# Schematic.net
KiCad netlist of a schematic drawn in Altium Designer
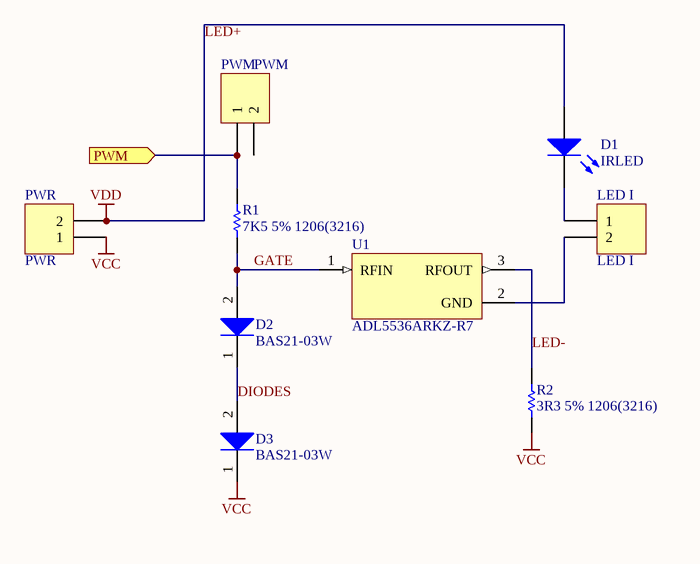
[diagram p0: Schematic.SchDoc]

(export (version "E")
  (design (tool "Eeschema 10.0.6"))
  (components
    (comp (ref "D1")
      (value "IRLED")
      (footprint "LED-1")
      (description "Typical RED GaAs LED")
      (fields (field (name "PUBLISHER") "Altium Limited"))
      (libsource (lib "Miscellaneous Devices") (part "LED1"))
    )
    (comp (ref "D2")
      (value "BAS21-03W")
      (footprint "INF-SOD323_V")
      (description "Silicon Switching Diode, SOD323, Reel, Green")
      (fields (field (name "MANUFACTURER") "Infineon"))
      (libsource (lib "Altium Inc") (part "CMP-1176-00009-1"))
    )
    (comp (ref "D3")
      (value "BAS21-03W")
      (footprint "INF-SOD323_V")
      (description "Silicon Switching Diode, SOD323, Reel, Green")
      (fields (field (name "MANUFACTURER") "Infineon"))
      (libsource (lib "Altium Inc") (part "CMP-1176-00009-1"))
    )
    (comp (ref "LED I")
      (value "LED I")
      (footprint "HDR1X2")
      (description "Header, 2-Pin")
      (fields (field (name "PUBLISHER") "Altium Limited"))
      (libsource (lib "Miscellaneous Connectors") (part "Header 2"))
    )
    (comp (ref "PWM")
      (value "PWM")
      (footprint "HDR1X2")
      (description "Header, 2-Pin")
      (fields (field (name "PUBLISHER") "Altium Limited"))
      (libsource (lib "") (part "Header 2_2"))
    )
    (comp (ref "PWR")
      (value "PWR")
      (footprint "HDR1X2")
      (description "Header, 2-Pin")
      (fields (field (name "PUBLISHER") "Altium Limited"))
      (libsource (lib "") (part "Header 2_1"))
    )
    (comp (ref "R1")
      (value "7K5 5% 1206(3216)")
      (footprint "RESC1206(3216)_N")
      (description "7K5 0.25W 5% 1206 (3216 Metric)  SMD")
      (fields (field (name "POWER") "0.25 W") (field (name "TOLERANCE") "5 %"))
      (libsource (lib "Altium Inc") (part "RES"))
    )
    (comp (ref "R2")
      (value "3R3 5% 1206(3216)")
      (footprint "RESC1206(3216)_L")
      (description "3R3 0.25W 5% 1206 (3216 Metric)  SMD")
      (fields (field (name "POWER") "0.25 W") (field (name "TOLERANCE") "5 %"))
      (libsource (lib "Altium Inc") (part "RES"))
    )
    (comp (ref "U1")
      (value "ADL5536ARKZ-R7")
      (footprint "ADI-RK-3_N")
      (description "20 MHz to 1.0 GHz IF Gain Block, 5.5V, RK-3, 1000 Reel, Pb-Free")
      (libsource (lib "Altium Inc") (part "CMP-0291-00032-1"))
    )
  )
  (nets
    (net (code "1") (name "/DIODES") (class "Default")
      (node (ref "D2") (pin "1") (pinfunction "K_1") (pintype "passive"))
      (node (ref "D3") (pin "2") (pinfunction "A_2") (pintype "passive"))
    )
    (net (code "2") (name "/GATE") (class "Default")
      (node (ref "D2") (pin "2") (pinfunction "A_2") (pintype "passive"))
      (node (ref "R1") (pin "1") (pinfunction "1_1") (pintype "passive"))
      (node (ref "U1") (pin "1") (pinfunction "RFIN_1") (pintype "input"))
    )
    (net (code "3") (name "/LED-") (class "Default")
      (node (ref "R2") (pin "2") (pinfunction "2_2") (pintype "passive"))
      (node (ref "U1") (pin "3") (pinfunction "RFOUT_3") (pintype "output"))
    )
    (net (code "4") (name "/PWM") (class "Default")
      (node (ref "PWM") (pin "1") (pinfunction "1_1") (pintype "passive"))
      (node (ref "R1") (pin "2") (pinfunction "2_2") (pintype "passive"))
    )
    (net (code "5") (name "Net-(D1-K)") (class "Default")
      (node (ref "D1") (pin "2") (pinfunction "K_2") (pintype "passive"))
      (node (ref "LED I") (pin "1") (pinfunction "1_1") (pintype "passive"))
    )
    (net (code "6") (name "Net-(U1-GND)") (class "Default")
      (node (ref "LED I") (pin "2") (pinfunction "2_2") (pintype "passive"))
      (node (ref "U1") (pin "2") (pinfunction "GND_2") (pintype "power_in"))
    )
    (net (code "7") (name "VCC") (class "Default")
      (node (ref "D3") (pin "1") (pinfunction "K_1") (pintype "passive"))
      (node (ref "PWR") (pin "1") (pinfunction "1_1") (pintype "passive"))
      (node (ref "R2") (pin "1") (pinfunction "1_1") (pintype "passive"))
    )
    (net (code "8") (name "VDD") (class "Default")
      (node (ref "D1") (pin "1") (pinfunction "A_1") (pintype "passive"))
      (node (ref "PWR") (pin "2") (pinfunction "2_2") (pintype "passive"))
    )
    (net (code "9") (name "unconnected-(PWM-Pad2)") (class "Default")
      (node (ref "PWM") (pin "2") (pinfunction "2_2") (pintype "passive"))
    )
  )
)
